# CompPhysMP_V1_0_1.net
KiCad netlist of a schematic drawn in EAGLE
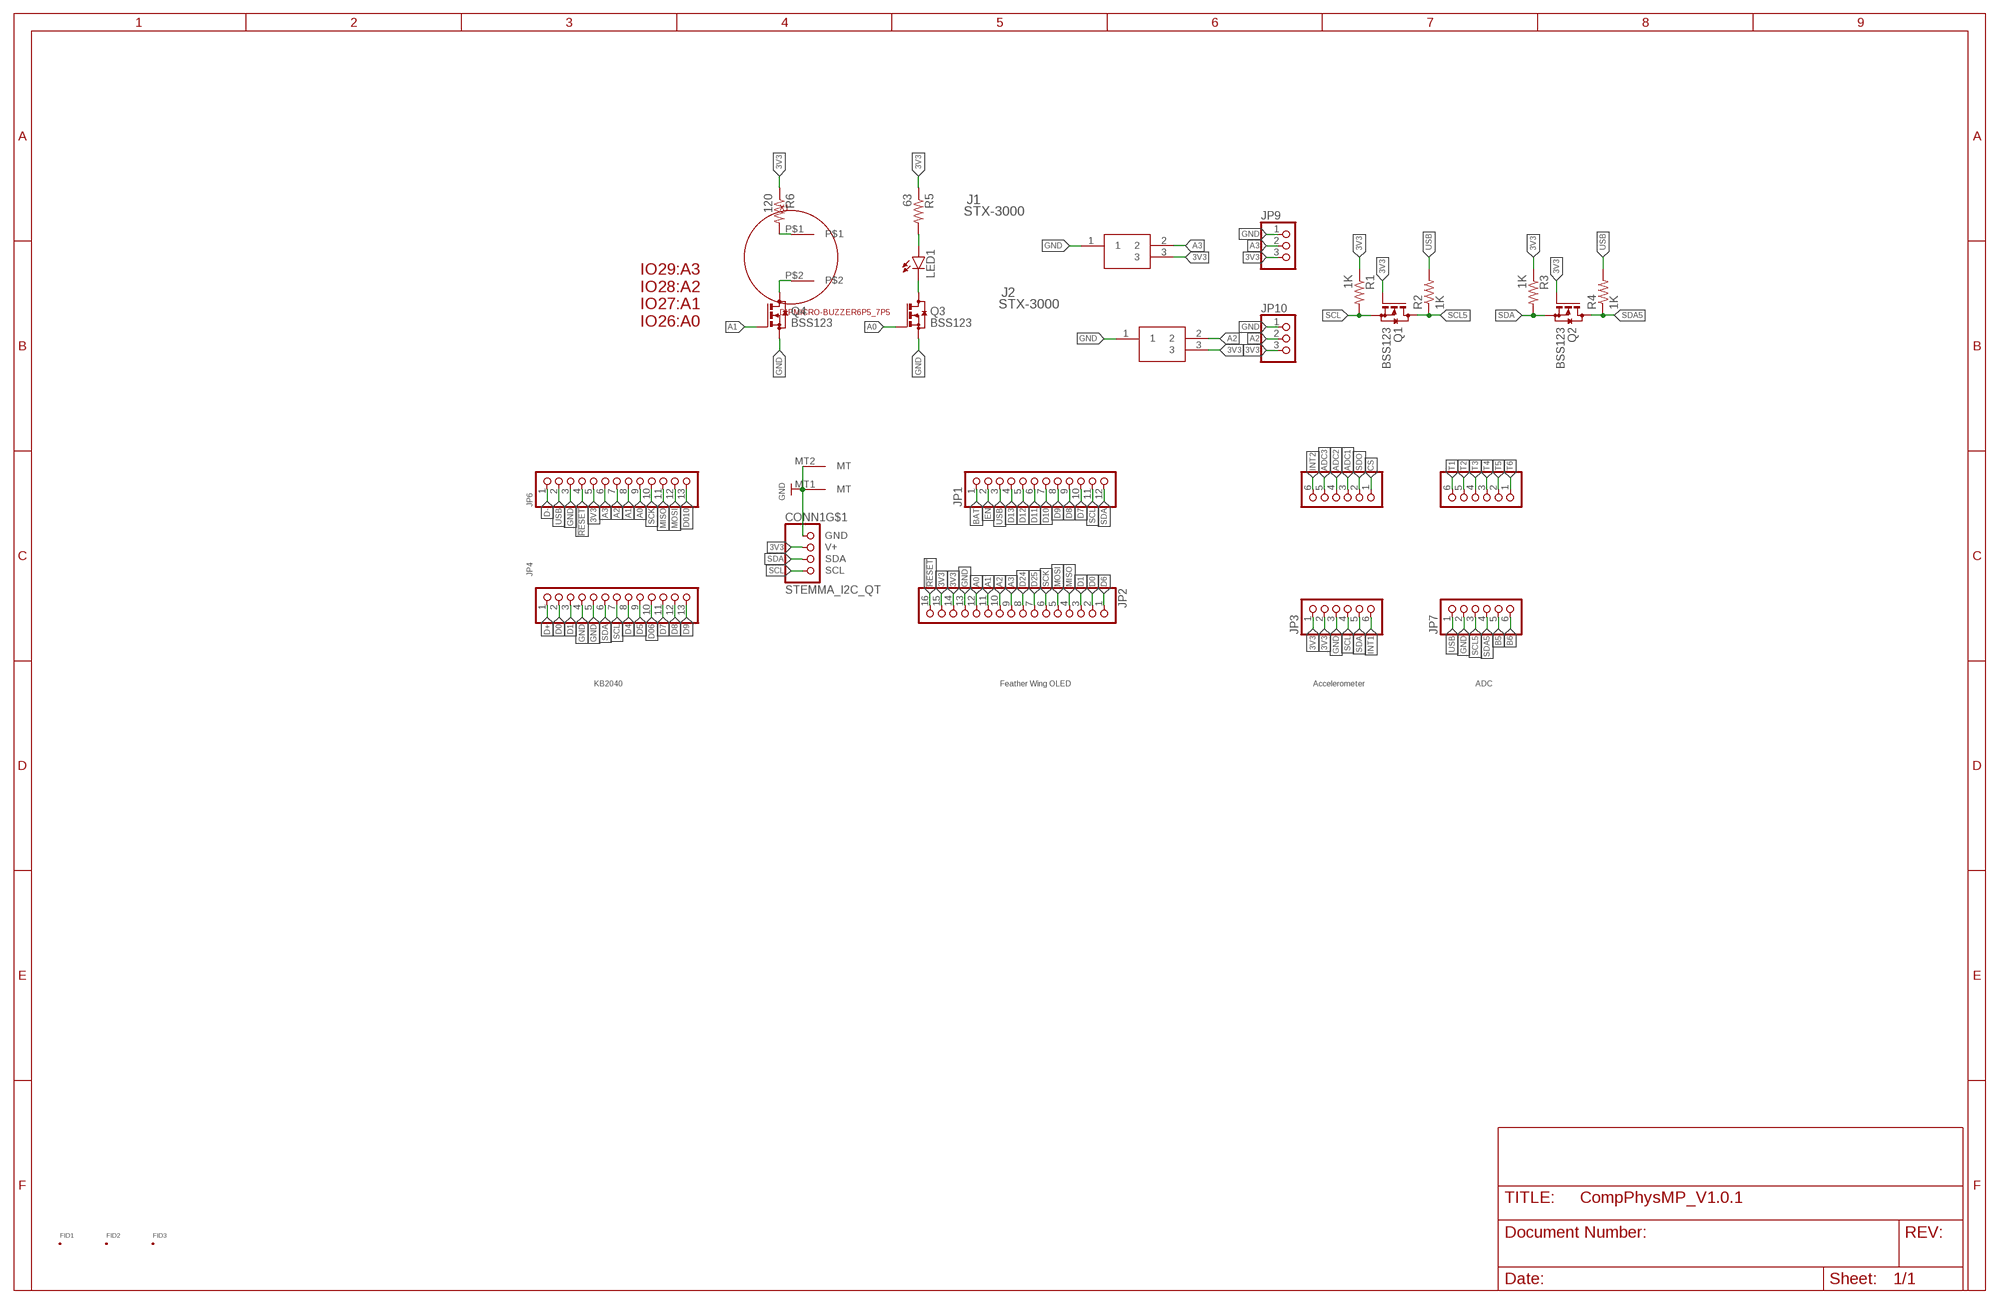
[diagram p0: schematic, sheet 1]

(export (version "E")
  (design (tool "Eeschema 10.0.6"))
  (components
    (comp (ref "CONN1")
      (value "STEMMA_I2C_QT")
      (footprint "eagle-import:JST_SH4")
      (libsource (lib "eagle-import") (part "STEMMA_I2C_QT"))
    )
    (comp (ref "FID1")
      (value "FID_50MIL")
      (footprint "eagle-import:FID_050")
      (libsource (lib "eagle-import") (part "FID_50MIL"))
    )
    (comp (ref "FID2")
      (value "FID_50MIL")
      (footprint "eagle-import:FID_050")
      (libsource (lib "eagle-import") (part "FID_50MIL"))
    )
    (comp (ref "FID3")
      (value "FID_50MIL")
      (footprint "eagle-import:FID_050")
      (libsource (lib "eagle-import") (part "FID_50MIL"))
    )
    (comp (ref "J1")
      (value "STX-3000")
      (footprint "eagle-import:STX3000")
      (fields (field (name "MOUSER_PART_NUMBER") "806-STX-3000"))
      (libsource (lib "eagle-import") (part "STX-3000"))
    )
    (comp (ref "J2")
      (value "STX-3000")
      (footprint "eagle-import:STX3000")
      (fields (field (name "MOUSER_PART_NUMBER") "806-STX-3000"))
      (libsource (lib "eagle-import") (part "STX-3000"))
    )
    (comp (ref "JP1")
      (value "PINHD-1X12")
      (footprint "eagle-import:1X12")
      (libsource (lib "eagle-import") (part "PINHD-1X12"))
    )
    (comp (ref "JP2")
      (value "PINHD-1X16")
      (footprint "eagle-import:1X16")
      (libsource (lib "eagle-import") (part "PINHD-1X16"))
    )
    (comp (ref "JP3")
      (value "HEADER-1X670MIL")
      (footprint "eagle-import:1X06_ROUND_70")
      (libsource (lib "eagle-import") (part "HEADER-1X670MIL"))
    )
    (comp (ref "JP4")
      (value "PINHD-1X13")
      (footprint "eagle-import:1X13")
      (libsource (lib "eagle-import") (part "PINHD-1X13"))
    )
    (comp (ref "JP5")
      (value "HEADER-1X670MIL")
      (footprint "eagle-import:1X06_ROUND_70")
      (libsource (lib "eagle-import") (part "HEADER-1X670MIL"))
    )
    (comp (ref "JP6")
      (value "PINHD-1X13")
      (footprint "eagle-import:1X13")
      (libsource (lib "eagle-import") (part "PINHD-1X13"))
    )
    (comp (ref "JP7")
      (value "HEADER-1X670MIL")
      (footprint "eagle-import:1X06_ROUND_70")
      (libsource (lib "eagle-import") (part "HEADER-1X670MIL"))
    )
    (comp (ref "JP8")
      (value "HEADER-1X670MIL")
      (footprint "eagle-import:1X06_ROUND_70")
      (libsource (lib "eagle-import") (part "HEADER-1X670MIL"))
    )
    (comp (ref "JP9")
      (value "PINHD-1X3SMALL-PADS")
      (footprint "eagle-import:1X03-BIG")
      (libsource (lib "eagle-import") (part "PINHD-1X3SMALL-PADS"))
    )
    (comp (ref "JP10")
      (value "PINHD-1X3SMALL-PADS")
      (footprint "eagle-import:1X03-BIG")
      (libsource (lib "eagle-import") (part "PINHD-1X3SMALL-PADS"))
    )
    (comp (ref "LED1")
      (value "LED5MM")
      (footprint "eagle-import:LED5MM")
      (libsource (lib "eagle-import") (part "LED5MM"))
    )
    (comp (ref "Q1")
      (value "BSS123")
      (footprint "eagle-import:SOT23")
      (libsource (lib "eagle-import") (part "BSS123"))
    )
    (comp (ref "Q2")
      (value "BSS123")
      (footprint "eagle-import:SOT23")
      (libsource (lib "eagle-import") (part "BSS123"))
    )
    (comp (ref "Q3")
      (value "BSS123")
      (footprint "eagle-import:SOT23")
      (libsource (lib "eagle-import") (part "BSS123"))
    )
    (comp (ref "Q4")
      (value "BSS123")
      (footprint "eagle-import:SOT23")
      (libsource (lib "eagle-import") (part "BSS123"))
    )
    (comp (ref "R1")
      (value "1K")
      (footprint "eagle-import:R0805")
      (libsource (lib "eagle-import") (part "R-US_R0805"))
    )
    (comp (ref "R2")
      (value "1K")
      (footprint "eagle-import:R0805")
      (libsource (lib "eagle-import") (part "R-US_R0805"))
    )
    (comp (ref "R3")
      (value "1K")
      (footprint "eagle-import:R0805")
      (libsource (lib "eagle-import") (part "R-US_R0805"))
    )
    (comp (ref "R4")
      (value "1K")
      (footprint "eagle-import:R0805")
      (libsource (lib "eagle-import") (part "R-US_R0805"))
    )
    (comp (ref "R5")
      (value "63")
      (footprint "eagle-import:R0805")
      (libsource (lib "eagle-import") (part "R-US_R0805"))
    )
    (comp (ref "R6")
      (value "120")
      (footprint "eagle-import:R0805")
      (libsource (lib "eagle-import") (part "R-US_R0805"))
    )
    (comp (ref "X1")
      (value "DIPMICRO-BUZZER6P5_7P5")
      (footprint "eagle-import:BUZZER-6P5-7P5")
      (libsource (lib "eagle-import") (part "DIPMICRO-BUZZER6P5_7P5"))
    )
  )
  (nets
    (net (code "1") (name "/~{RESET}") (class "Default")
      (node (ref "JP2") (pin "16") (pinfunction "16_16") (pintype "passive"))
      (node (ref "JP6") (pin "4") (pinfunction "4_4") (pintype "passive"))
    )
    (net (code "2") (name "3V3") (class "Default")
      (node (ref "CONN1") (pin "2") (pinfunction "V+_2") (pintype "passive"))
      (node (ref "J1") (pin "3") (pinfunction "3_3") (pintype "bidirectional"))
      (node (ref "J2") (pin "3") (pinfunction "3_3") (pintype "bidirectional"))
      (node (ref "JP10") (pin "3") (pinfunction "3_3") (pintype "passive"))
      (node (ref "JP2") (pin "14") (pinfunction "14_14") (pintype "passive"))
      (node (ref "JP2") (pin "15") (pinfunction "15_15") (pintype "passive"))
      (node (ref "JP3") (pin "1") (pinfunction "1_1") (pintype "passive"))
      (node (ref "JP3") (pin "2") (pinfunction "2_2") (pintype "passive"))
      (node (ref "JP6") (pin "5") (pinfunction "5_5") (pintype "passive"))
      (node (ref "JP9") (pin "3") (pinfunction "3_3") (pintype "passive"))
      (node (ref "Q1") (pin "1") (pinfunction "G_1") (pintype "passive"))
      (node (ref "Q2") (pin "1") (pinfunction "G_1") (pintype "passive"))
      (node (ref "R1") (pin "1") (pinfunction "1_1") (pintype "passive"))
      (node (ref "R3") (pin "1") (pinfunction "1_1") (pintype "passive"))
      (node (ref "R5") (pin "1") (pinfunction "1_1") (pintype "passive"))
      (node (ref "R6") (pin "1") (pinfunction "1_1") (pintype "passive"))
    )
    (net (code "3") (name "A0") (class "Default")
      (node (ref "JP2") (pin "12") (pinfunction "12_12") (pintype "passive"))
      (node (ref "JP6") (pin "9") (pinfunction "9_9") (pintype "passive"))
      (node (ref "Q3") (pin "1") (pinfunction "G_1") (pintype "passive"))
    )
    (net (code "4") (name "A1") (class "Default")
      (node (ref "JP2") (pin "11") (pinfunction "11_11") (pintype "passive"))
      (node (ref "JP6") (pin "8") (pinfunction "8_8") (pintype "passive"))
      (node (ref "Q4") (pin "1") (pinfunction "G_1") (pintype "passive"))
    )
    (net (code "5") (name "A2") (class "Default")
      (node (ref "J2") (pin "2") (pinfunction "2_2") (pintype "bidirectional"))
      (node (ref "JP10") (pin "2") (pinfunction "2_2") (pintype "passive"))
      (node (ref "JP2") (pin "10") (pinfunction "10_10") (pintype "passive"))
      (node (ref "JP6") (pin "7") (pinfunction "7_7") (pintype "passive"))
    )
    (net (code "6") (name "A3") (class "Default")
      (node (ref "J1") (pin "2") (pinfunction "2_2") (pintype "bidirectional"))
      (node (ref "JP2") (pin "9") (pinfunction "9_9") (pintype "passive"))
      (node (ref "JP6") (pin "6") (pinfunction "6_6") (pintype "passive"))
      (node (ref "JP9") (pin "2") (pinfunction "2_2") (pintype "passive"))
    )
    (net (code "7") (name "ADC1") (class "Default")
      (node (ref "JP5") (pin "3") (pinfunction "3_3") (pintype "passive"))
    )
    (net (code "8") (name "ADC2") (class "Default")
      (node (ref "JP5") (pin "4") (pinfunction "4_4") (pintype "passive"))
    )
    (net (code "9") (name "ADC3") (class "Default")
      (node (ref "JP5") (pin "5") (pinfunction "5_5") (pintype "passive"))
    )
    (net (code "10") (name "B5") (class "Default")
      (node (ref "JP7") (pin "5") (pinfunction "5_5") (pintype "passive"))
    )
    (net (code "11") (name "B6") (class "Default")
      (node (ref "JP7") (pin "6") (pinfunction "6_6") (pintype "passive"))
    )
    (net (code "12") (name "BAT") (class "Default")
      (node (ref "JP1") (pin "1") (pinfunction "1_1") (pintype "passive"))
    )
    (net (code "13") (name "CS") (class "Default")
      (node (ref "JP5") (pin "1") (pinfunction "1_1") (pintype "passive"))
    )
    (net (code "14") (name "D+") (class "Default")
      (node (ref "JP4") (pin "1") (pinfunction "1_1") (pintype "passive"))
    )
    (net (code "15") (name "D-") (class "Default")
      (node (ref "JP6") (pin "1") (pinfunction "1_1") (pintype "passive"))
    )
    (net (code "16") (name "D0") (class "Default")
      (node (ref "JP2") (pin "2") (pinfunction "2_2") (pintype "passive"))
      (node (ref "JP4") (pin "2") (pinfunction "2_2") (pintype "passive"))
    )
    (net (code "17") (name "D1") (class "Default")
      (node (ref "JP2") (pin "3") (pinfunction "3_3") (pintype "passive"))
      (node (ref "JP4") (pin "3") (pinfunction "3_3") (pintype "passive"))
    )
    (net (code "18") (name "D4") (class "Default")
      (node (ref "JP4") (pin "8") (pinfunction "8_8") (pintype "passive"))
    )
    (net (code "19") (name "D5") (class "Default")
      (node (ref "JP4") (pin "9") (pinfunction "9_9") (pintype "passive"))
    )
    (net (code "20") (name "D06") (class "Default")
      (node (ref "JP4") (pin "10") (pinfunction "10_10") (pintype "passive"))
    )
    (net (code "21") (name "D6") (class "Default")
      (node (ref "JP2") (pin "1") (pinfunction "1_1") (pintype "passive"))
    )
    (net (code "22") (name "D7") (class "Default")
      (node (ref "JP1") (pin "10") (pinfunction "10_10") (pintype "passive"))
      (node (ref "JP4") (pin "11") (pinfunction "11_11") (pintype "passive"))
    )
    (net (code "23") (name "D8") (class "Default")
      (node (ref "JP1") (pin "9") (pinfunction "9_9") (pintype "passive"))
      (node (ref "JP4") (pin "12") (pinfunction "12_12") (pintype "passive"))
    )
    (net (code "24") (name "D9") (class "Default")
      (node (ref "JP1") (pin "8") (pinfunction "8_8") (pintype "passive"))
      (node (ref "JP4") (pin "13") (pinfunction "13_13") (pintype "passive"))
    )
    (net (code "25") (name "D010") (class "Default")
      (node (ref "JP6") (pin "13") (pinfunction "13_13") (pintype "passive"))
    )
    (net (code "26") (name "D10") (class "Default")
      (node (ref "JP1") (pin "7") (pinfunction "7_7") (pintype "passive"))
    )
    (net (code "27") (name "D11") (class "Default")
      (node (ref "JP1") (pin "6") (pinfunction "6_6") (pintype "passive"))
    )
    (net (code "28") (name "D12") (class "Default")
      (node (ref "JP1") (pin "5") (pinfunction "5_5") (pintype "passive"))
    )
    (net (code "29") (name "D13") (class "Default")
      (node (ref "JP1") (pin "4") (pinfunction "4_4") (pintype "passive"))
    )
    (net (code "30") (name "D24") (class "Default")
      (node (ref "JP2") (pin "8") (pinfunction "8_8") (pintype "passive"))
    )
    (net (code "31") (name "D25") (class "Default")
      (node (ref "JP2") (pin "7") (pinfunction "7_7") (pintype "passive"))
    )
    (net (code "32") (name "EN") (class "Default")
      (node (ref "JP1") (pin "2") (pinfunction "2_2") (pintype "passive"))
    )
    (net (code "33") (name "GND") (class "Default")
      (node (ref "CONN1") (pin "1") (pinfunction "GND_1") (pintype "passive"))
      (node (ref "CONN1") (pin "MT1") (pinfunction "MT_MT1") (pintype "bidirectional"))
      (node (ref "CONN1") (pin "MT2") (pinfunction "MT_MT2") (pintype "bidirectional"))
      (node (ref "J1") (pin "1") (pinfunction "1_1") (pintype "bidirectional"))
      (node (ref "J2") (pin "1") (pinfunction "1_1") (pintype "bidirectional"))
      (node (ref "JP10") (pin "1") (pinfunction "1_1") (pintype "passive"))
      (node (ref "JP2") (pin "13") (pinfunction "13_13") (pintype "passive"))
      (node (ref "JP3") (pin "3") (pinfunction "3_3") (pintype "passive"))
      (node (ref "JP4") (pin "4") (pinfunction "4_4") (pintype "passive"))
      (node (ref "JP4") (pin "5") (pinfunction "5_5") (pintype "passive"))
      (node (ref "JP6") (pin "3") (pinfunction "3_3") (pintype "passive"))
      (node (ref "JP7") (pin "2") (pinfunction "2_2") (pintype "passive"))
      (node (ref "JP9") (pin "1") (pinfunction "1_1") (pintype "passive"))
      (node (ref "Q3") (pin "2") (pinfunction "S_2") (pintype "passive"))
      (node (ref "Q4") (pin "2") (pinfunction "S_2") (pintype "passive"))
    )
    (net (code "34") (name "INT1") (class "Default")
      (node (ref "JP3") (pin "6") (pinfunction "6_6") (pintype "passive"))
    )
    (net (code "35") (name "INT2") (class "Default")
      (node (ref "JP5") (pin "6") (pinfunction "6_6") (pintype "passive"))
    )
    (net (code "36") (name "MISO") (class "Default")
      (node (ref "JP2") (pin "4") (pinfunction "4_4") (pintype "passive"))
      (node (ref "JP6") (pin "11") (pinfunction "11_11") (pintype "passive"))
    )
    (net (code "37") (name "MOSI") (class "Default")
      (node (ref "JP2") (pin "5") (pinfunction "5_5") (pintype "passive"))
      (node (ref "JP6") (pin "12") (pinfunction "12_12") (pintype "passive"))
    )
    (net (code "38") (name "Net-(LED1-C)") (class "Default")
      (node (ref "LED1") (pin "K") (pinfunction "C_K") (pintype "passive"))
      (node (ref "Q3") (pin "3") (pinfunction "D_3") (pintype "passive"))
    )
    (net (code "39") (name "Net-(LED1-PadA)") (class "Default")
      (node (ref "LED1") (pin "A") (pinfunction "A_A") (pintype "passive"))
      (node (ref "R5") (pin "2") (pinfunction "2_2") (pintype "passive"))
    )
    (net (code "40") (name "Net-(Q4-D)") (class "Default")
      (node (ref "Q4") (pin "3") (pinfunction "D_3") (pintype "passive"))
      (node (ref "X1") (pin "P$2") (pinfunction "P$2_P$2") (pintype "bidirectional"))
    )
    (net (code "41") (name "Net-(R6-Pad2)") (class "Default")
      (node (ref "R6") (pin "2") (pinfunction "2_2") (pintype "passive"))
      (node (ref "X1") (pin "P$1") (pinfunction "P$1_P$1") (pintype "bidirectional"))
    )
    (net (code "42") (name "SCK") (class "Default")
      (node (ref "JP2") (pin "6") (pinfunction "6_6") (pintype "passive"))
      (node (ref "JP6") (pin "10") (pinfunction "10_10") (pintype "passive"))
    )
    (net (code "43") (name "SCL") (class "Default")
      (node (ref "CONN1") (pin "4") (pinfunction "SCL_4") (pintype "passive"))
      (node (ref "JP1") (pin "11") (pinfunction "11_11") (pintype "passive"))
      (node (ref "JP3") (pin "4") (pinfunction "4_4") (pintype "passive"))
      (node (ref "JP4") (pin "7") (pinfunction "7_7") (pintype "passive"))
      (node (ref "Q1") (pin "2") (pinfunction "S_2") (pintype "passive"))
      (node (ref "R1") (pin "2") (pinfunction "2_2") (pintype "passive"))
    )
    (net (code "44") (name "SCL5") (class "Default")
      (node (ref "JP7") (pin "3") (pinfunction "3_3") (pintype "passive"))
      (node (ref "Q1") (pin "3") (pinfunction "D_3") (pintype "passive"))
      (node (ref "R2") (pin "1") (pinfunction "1_1") (pintype "passive"))
    )
    (net (code "45") (name "SDA") (class "Default")
      (node (ref "CONN1") (pin "3") (pinfunction "SDA_3") (pintype "passive"))
      (node (ref "JP1") (pin "12") (pinfunction "12_12") (pintype "passive"))
      (node (ref "JP3") (pin "5") (pinfunction "5_5") (pintype "passive"))
      (node (ref "JP4") (pin "6") (pinfunction "6_6") (pintype "passive"))
      (node (ref "Q2") (pin "2") (pinfunction "S_2") (pintype "passive"))
      (node (ref "R3") (pin "2") (pinfunction "2_2") (pintype "passive"))
    )
    (net (code "46") (name "SDA5") (class "Default")
      (node (ref "JP7") (pin "4") (pinfunction "4_4") (pintype "passive"))
      (node (ref "Q2") (pin "3") (pinfunction "D_3") (pintype "passive"))
      (node (ref "R4") (pin "1") (pinfunction "1_1") (pintype "passive"))
    )
    (net (code "47") (name "SDO") (class "Default")
      (node (ref "JP5") (pin "2") (pinfunction "2_2") (pintype "passive"))
    )
    (net (code "48") (name "T1") (class "Default")
      (node (ref "JP8") (pin "6") (pinfunction "6_6") (pintype "passive"))
    )
    (net (code "49") (name "T2") (class "Default")
      (node (ref "JP8") (pin "5") (pinfunction "5_5") (pintype "passive"))
    )
    (net (code "50") (name "T3") (class "Default")
      (node (ref "JP8") (pin "4") (pinfunction "4_4") (pintype "passive"))
    )
    (net (code "51") (name "T4") (class "Default")
      (node (ref "JP8") (pin "3") (pinfunction "3_3") (pintype "passive"))
    )
    (net (code "52") (name "T5") (class "Default")
      (node (ref "JP8") (pin "2") (pinfunction "2_2") (pintype "passive"))
    )
    (net (code "53") (name "T6") (class "Default")
      (node (ref "JP8") (pin "1") (pinfunction "1_1") (pintype "passive"))
    )
    (net (code "54") (name "USB") (class "Default")
      (node (ref "JP1") (pin "3") (pinfunction "3_3") (pintype "passive"))
      (node (ref "JP6") (pin "2") (pinfunction "2_2") (pintype "passive"))
      (node (ref "JP7") (pin "1") (pinfunction "1_1") (pintype "passive"))
      (node (ref "R2") (pin "2") (pinfunction "2_2") (pintype "passive"))
      (node (ref "R4") (pin "2") (pinfunction "2_2") (pintype "passive"))
    )
  )
)
